# schematic_V3.net
KiCad netlist of a schematic drawn in EAGLE
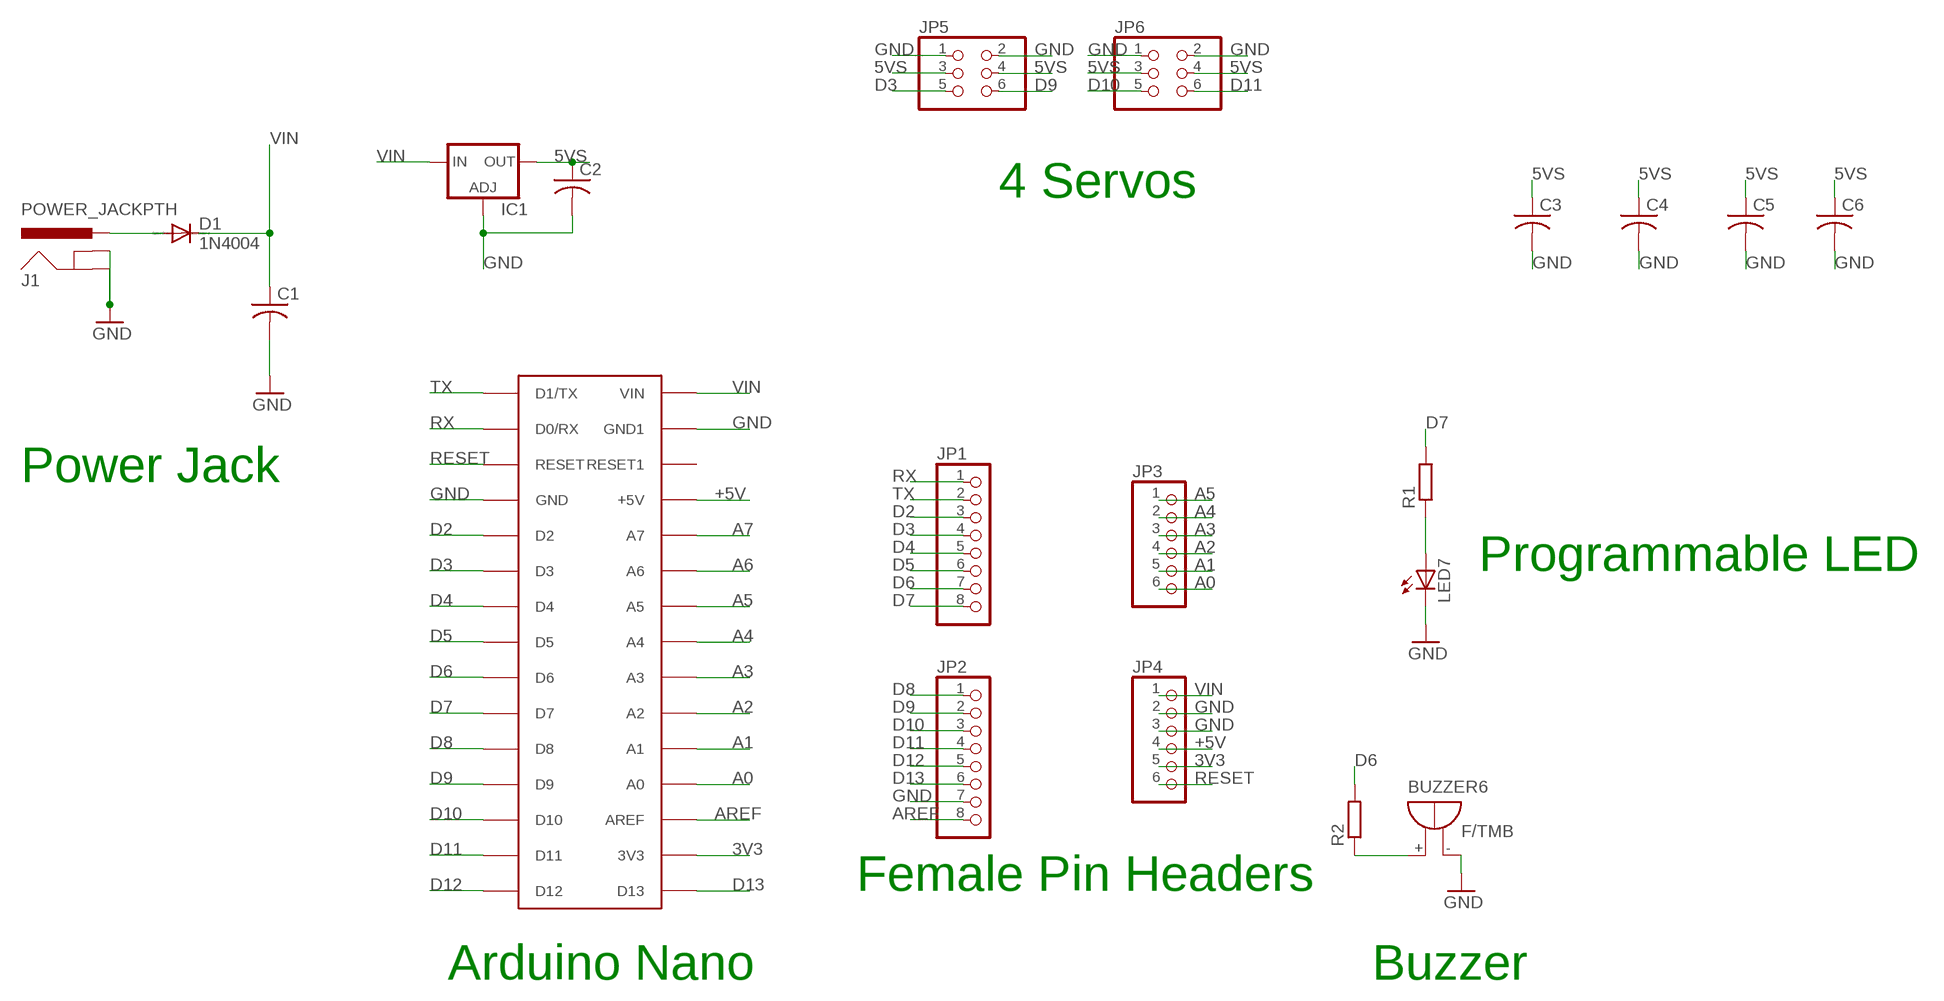
[diagram p0: schematic, sheet 1]

(export (version "E")
  (design (tool "Eeschema 10.0.6"))
  (components
    (comp (ref "BUZZER6")
      (value "F/TMB")
      (footprint "eagle-import:F_TMB")
      (libsource (lib "eagle-import") (part "F/TMB"))
    )
    (comp (ref "C1")
      (value "C-USC1206")
      (footprint "eagle-import:C1206")
      (libsource (lib "eagle-import") (part "C-USC1206"))
    )
    (comp (ref "C2")
      (value "C-USC1206")
      (footprint "eagle-import:C1206")
      (libsource (lib "eagle-import") (part "C-USC1206"))
    )
    (comp (ref "C3")
      (value "C-USC1206")
      (footprint "eagle-import:C1206")
      (libsource (lib "eagle-import") (part "C-USC1206"))
    )
    (comp (ref "C4")
      (value "C-USC1206")
      (footprint "eagle-import:C1206")
      (libsource (lib "eagle-import") (part "C-USC1206"))
    )
    (comp (ref "C5")
      (value "C-USC1206")
      (footprint "eagle-import:C1206")
      (libsource (lib "eagle-import") (part "C-USC1206"))
    )
    (comp (ref "C6")
      (value "C-USC1206")
      (footprint "eagle-import:C1206")
      (libsource (lib "eagle-import") (part "C-USC1206"))
    )
    (comp (ref "D1")
      (value "1N4004")
      (footprint "eagle-import:DO41-10")
      (libsource (lib "eagle-import") (part "1N4004"))
    )
    (comp (ref "IC1")
      (value "VR1")
      (footprint "eagle-import:SOT223")
      (libsource (lib "eagle-import") (part "LD117A?S33TR"))
    )
    (comp (ref "J1")
      (value "POWER_JACKPTH")
      (footprint "eagle-import:POWER_JACK_PTH")
      (libsource (lib "eagle-import") (part "POWER_JACKPTH"))
    )
    (comp (ref "JP1")
      (value "PINHD-1X8")
      (footprint "eagle-import:1X08")
      (libsource (lib "eagle-import") (part "PINHD-1X8"))
    )
    (comp (ref "JP2")
      (value "PINHD-1X8")
      (footprint "eagle-import:1X08")
      (libsource (lib "eagle-import") (part "PINHD-1X8"))
    )
    (comp (ref "JP3")
      (value "PINHD-1X6")
      (footprint "eagle-import:1X06")
      (libsource (lib "eagle-import") (part "PINHD-1X6"))
    )
    (comp (ref "JP4")
      (value "PINHD-1X6")
      (footprint "eagle-import:1X06")
      (libsource (lib "eagle-import") (part "PINHD-1X6"))
    )
    (comp (ref "JP5")
      (value "PINHD-2X3")
      (footprint "eagle-import:2X03")
      (libsource (lib "eagle-import") (part "PINHD-2X3"))
    )
    (comp (ref "JP6")
      (value "PINHD-2X3")
      (footprint "eagle-import:2X03")
      (libsource (lib "eagle-import") (part "PINHD-2X3"))
    )
    (comp (ref "LED7")
      (value "LED5MM")
      (footprint "eagle-import:LED5MM")
      (libsource (lib "eagle-import") (part "LED5MM"))
    )
    (comp (ref "R1")
      (value "R-EU_0207/10")
      (footprint "eagle-import:0207_10")
      (libsource (lib "eagle-import") (part "R-EU_0207/10"))
    )
    (comp (ref "R2")
      (value "R-EU_0207/10")
      (footprint "eagle-import:0207_10")
      (libsource (lib "eagle-import") (part "R-EU_0207/10"))
    )
    (comp (ref "U$1")
      (value "ARDUINONANO")
      (footprint "eagle-import:PDIP-32")
      (libsource (lib "eagle-import") (part "ARDUINONANO"))
    )
  )
  (nets
    (net (code "1") (name "/+5V") (class "Default")
      (node (ref "JP4") (pin "4") (pinfunction "4_4") (pintype "passive"))
      (node (ref "U$1") (pin "+5V") (pinfunction "+5V_+5V") (pintype "bidirectional"))
    )
    (net (code "2") (name "/3V3") (class "Default")
      (node (ref "JP4") (pin "5") (pinfunction "5_5") (pintype "passive"))
      (node (ref "U$1") (pin "3V3") (pinfunction "3V3_3V3") (pintype "bidirectional"))
    )
    (net (code "3") (name "/5VS") (class "Default")
      (node (ref "C2") (pin "1") (pinfunction "1_1") (pintype "passive"))
      (node (ref "C3") (pin "1") (pinfunction "1_1") (pintype "passive"))
      (node (ref "C4") (pin "1") (pinfunction "1_1") (pintype "passive"))
      (node (ref "C5") (pin "1") (pinfunction "1_1") (pintype "passive"))
      (node (ref "C6") (pin "1") (pinfunction "1_1") (pintype "passive"))
      (node (ref "IC1") (pin "4") (pinfunction "OUT_4") (pintype "passive"))
      (node (ref "JP5") (pin "3") (pinfunction "3_3") (pintype "passive"))
      (node (ref "JP5") (pin "4") (pinfunction "4_4") (pintype "passive"))
      (node (ref "JP6") (pin "3") (pinfunction "3_3") (pintype "passive"))
      (node (ref "JP6") (pin "4") (pinfunction "4_4") (pintype "passive"))
    )
    (net (code "4") (name "/A0") (class "Default")
      (node (ref "JP3") (pin "6") (pinfunction "6_6") (pintype "passive"))
      (node (ref "U$1") (pin "A7") (pinfunction "A0_A7") (pintype "bidirectional"))
    )
    (net (code "5") (name "/A1") (class "Default")
      (node (ref "JP3") (pin "5") (pinfunction "5_5") (pintype "passive"))
      (node (ref "U$1") (pin "A6") (pinfunction "A1_A6") (pintype "bidirectional"))
    )
    (net (code "6") (name "/A2") (class "Default")
      (node (ref "JP3") (pin "4") (pinfunction "4_4") (pintype "passive"))
      (node (ref "U$1") (pin "A5") (pinfunction "A2_A5") (pintype "bidirectional"))
    )
    (net (code "7") (name "/A3") (class "Default")
      (node (ref "JP3") (pin "3") (pinfunction "3_3") (pintype "passive"))
      (node (ref "U$1") (pin "A4") (pinfunction "A3_A4") (pintype "bidirectional"))
    )
    (net (code "8") (name "/A4") (class "Default")
      (node (ref "JP3") (pin "2") (pinfunction "2_2") (pintype "passive"))
      (node (ref "U$1") (pin "A3") (pinfunction "A4_A3") (pintype "bidirectional"))
    )
    (net (code "9") (name "/A5") (class "Default")
      (node (ref "JP3") (pin "1") (pinfunction "1_1") (pintype "passive"))
      (node (ref "U$1") (pin "A2") (pinfunction "A5_A2") (pintype "bidirectional"))
    )
    (net (code "10") (name "/A6") (class "Default")
      (node (ref "U$1") (pin "A1") (pinfunction "A6_A1") (pintype "bidirectional"))
    )
    (net (code "11") (name "/A7") (class "Default")
      (node (ref "U$1") (pin "A0") (pinfunction "A7_A0") (pintype "bidirectional"))
    )
    (net (code "12") (name "/AREF") (class "Default")
      (node (ref "JP2") (pin "8") (pinfunction "8_8") (pintype "passive"))
      (node (ref "U$1") (pin "AREF") (pinfunction "AREF_AREF") (pintype "bidirectional"))
    )
    (net (code "13") (name "/D2") (class "Default")
      (node (ref "JP1") (pin "3") (pinfunction "3_3") (pintype "passive"))
      (node (ref "U$1") (pin "D2") (pinfunction "D2_D2") (pintype "bidirectional"))
    )
    (net (code "14") (name "/D3") (class "Default")
      (node (ref "JP1") (pin "4") (pinfunction "4_4") (pintype "passive"))
      (node (ref "JP5") (pin "5") (pinfunction "5_5") (pintype "passive"))
      (node (ref "U$1") (pin "D3") (pinfunction "D3_D3") (pintype "bidirectional"))
    )
    (net (code "15") (name "/D4") (class "Default")
      (node (ref "JP1") (pin "5") (pinfunction "5_5") (pintype "passive"))
      (node (ref "U$1") (pin "D4") (pinfunction "D4_D4") (pintype "bidirectional"))
    )
    (net (code "16") (name "/D5") (class "Default")
      (node (ref "JP1") (pin "6") (pinfunction "6_6") (pintype "passive"))
      (node (ref "U$1") (pin "D5") (pinfunction "D5_D5") (pintype "bidirectional"))
    )
    (net (code "17") (name "/D6") (class "Default")
      (node (ref "JP1") (pin "7") (pinfunction "7_7") (pintype "passive"))
      (node (ref "R2") (pin "2") (pinfunction "2_2") (pintype "passive"))
      (node (ref "U$1") (pin "D6") (pinfunction "D6_D6") (pintype "bidirectional"))
    )
    (net (code "18") (name "/D7") (class "Default")
      (node (ref "JP1") (pin "8") (pinfunction "8_8") (pintype "passive"))
      (node (ref "R1") (pin "2") (pinfunction "2_2") (pintype "passive"))
      (node (ref "U$1") (pin "D7") (pinfunction "D7_D7") (pintype "bidirectional"))
    )
    (net (code "19") (name "/D8") (class "Default")
      (node (ref "JP2") (pin "1") (pinfunction "1_1") (pintype "passive"))
      (node (ref "U$1") (pin "D8") (pinfunction "D8_D8") (pintype "bidirectional"))
    )
    (net (code "20") (name "/D9") (class "Default")
      (node (ref "JP2") (pin "2") (pinfunction "2_2") (pintype "passive"))
      (node (ref "JP5") (pin "6") (pinfunction "6_6") (pintype "passive"))
      (node (ref "U$1") (pin "D9") (pinfunction "D9_D9") (pintype "bidirectional"))
    )
    (net (code "21") (name "/D10") (class "Default")
      (node (ref "JP2") (pin "3") (pinfunction "3_3") (pintype "passive"))
      (node (ref "JP6") (pin "5") (pinfunction "5_5") (pintype "passive"))
      (node (ref "U$1") (pin "D10") (pinfunction "D10_D10") (pintype "bidirectional"))
    )
    (net (code "22") (name "/D11") (class "Default")
      (node (ref "JP2") (pin "4") (pinfunction "4_4") (pintype "passive"))
      (node (ref "JP6") (pin "6") (pinfunction "6_6") (pintype "passive"))
      (node (ref "U$1") (pin "D11") (pinfunction "D11_D11") (pintype "bidirectional"))
    )
    (net (code "23") (name "/D12") (class "Default")
      (node (ref "JP2") (pin "5") (pinfunction "5_5") (pintype "passive"))
      (node (ref "U$1") (pin "D12") (pinfunction "D12_D12") (pintype "bidirectional"))
    )
    (net (code "24") (name "/D13") (class "Default")
      (node (ref "JP2") (pin "6") (pinfunction "6_6") (pintype "passive"))
      (node (ref "U$1") (pin "D13") (pinfunction "D13_D13") (pintype "bidirectional"))
    )
    (net (code "25") (name "/RESET") (class "Default")
      (node (ref "JP4") (pin "6") (pinfunction "6_6") (pintype "passive"))
      (node (ref "U$1") (pin "RESET") (pinfunction "RESET_RESET") (pintype "bidirectional"))
    )
    (net (code "26") (name "/RX") (class "Default")
      (node (ref "JP1") (pin "1") (pinfunction "1_1") (pintype "passive"))
      (node (ref "U$1") (pin "D0/RX") (pinfunction "D0/RX_D0/RX") (pintype "bidirectional"))
    )
    (net (code "27") (name "/TX") (class "Default")
      (node (ref "JP1") (pin "2") (pinfunction "2_2") (pintype "passive"))
      (node (ref "U$1") (pin "D1/TX") (pinfunction "D1/TX_D1/TX") (pintype "bidirectional"))
    )
    (net (code "28") (name "/VIN") (class "Default")
      (node (ref "C1") (pin "1") (pinfunction "1_1") (pintype "passive"))
      (node (ref "D1") (pin "C") (pinfunction "C_C") (pintype "passive"))
      (node (ref "IC1") (pin "3") (pinfunction "IN_3") (pintype "input"))
      (node (ref "JP4") (pin "1") (pinfunction "1_1") (pintype "passive"))
      (node (ref "U$1") (pin "VIN") (pinfunction "VIN_VIN") (pintype "bidirectional"))
    )
    (net (code "29") (name "GND") (class "Default")
      (node (ref "BUZZER6") (pin "-") (pinfunction "-_-") (pintype "passive"))
      (node (ref "C1") (pin "2") (pinfunction "2_2") (pintype "passive"))
      (node (ref "C2") (pin "2") (pinfunction "2_2") (pintype "passive"))
      (node (ref "C3") (pin "2") (pinfunction "2_2") (pintype "passive"))
      (node (ref "C4") (pin "2") (pinfunction "2_2") (pintype "passive"))
      (node (ref "C5") (pin "2") (pinfunction "2_2") (pintype "passive"))
      (node (ref "C6") (pin "2") (pinfunction "2_2") (pintype "passive"))
      (node (ref "IC1") (pin "1") (pinfunction "ADJ_1") (pintype "input"))
      (node (ref "J1") (pin "GND") (pinfunction "GND_GND") (pintype "bidirectional"))
      (node (ref "J1") (pin "GNDBREAK") (pinfunction "GNDBREAK_GNDBREAK") (pintype "bidirectional"))
      (node (ref "JP2") (pin "7") (pinfunction "7_7") (pintype "passive"))
      (node (ref "JP4") (pin "2") (pinfunction "2_2") (pintype "passive"))
      (node (ref "JP4") (pin "3") (pinfunction "3_3") (pintype "passive"))
      (node (ref "JP5") (pin "1") (pinfunction "1_1") (pintype "passive"))
      (node (ref "JP5") (pin "2") (pinfunction "2_2") (pintype "passive"))
      (node (ref "JP6") (pin "1") (pinfunction "1_1") (pintype "passive"))
      (node (ref "JP6") (pin "2") (pinfunction "2_2") (pintype "passive"))
      (node (ref "LED7") (pin "K") (pinfunction "C_K") (pintype "passive"))
      (node (ref "U$1") (pin "GND") (pinfunction "GND_GND") (pintype "bidirectional"))
      (node (ref "U$1") (pin "GND1") (pinfunction "GND1_GND1") (pintype "bidirectional"))
    )
    (net (code "30") (name "Net-(BUZZER6-Pad+)") (class "Default")
      (node (ref "BUZZER6") (pin "+") (pinfunction "+_+") (pintype "passive"))
      (node (ref "R2") (pin "1") (pinfunction "1_1") (pintype "passive"))
    )
    (net (code "31") (name "Net-(D1-PadA)") (class "Default")
      (node (ref "D1") (pin "A") (pinfunction "A_A") (pintype "passive"))
      (node (ref "J1") (pin "PWR") (pinfunction "PWR_PWR") (pintype "bidirectional"))
    )
    (net (code "32") (name "Net-(LED7-PadA)") (class "Default")
      (node (ref "LED7") (pin "A") (pinfunction "A_A") (pintype "passive"))
      (node (ref "R1") (pin "1") (pinfunction "1_1") (pintype "passive"))
    )
    (net (code "33") (name "unconnected-(U$1-PadRESET1)") (class "Default")
      (node (ref "U$1") (pin "RESET1") (pinfunction "RESET1_RESET1") (pintype "bidirectional"))
    )
  )
)
